# LightBarrier.net
KiCad netlist of a schematic drawn in Altium Designer
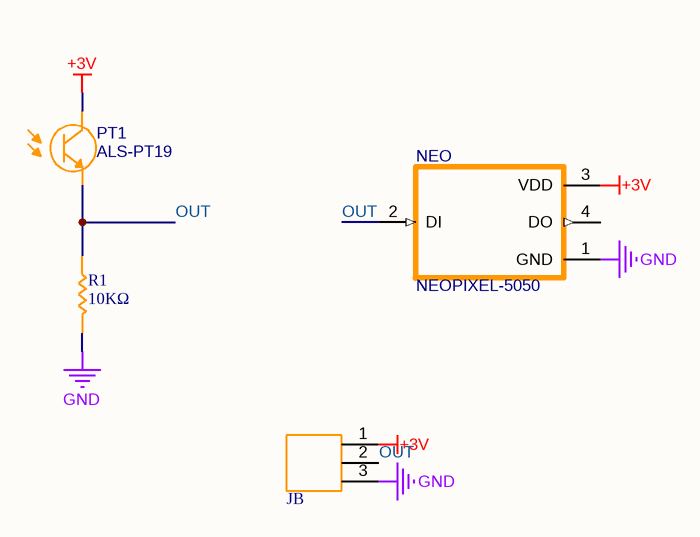
[diagram p0: LightBarrier.SchDoc]

(export (version "E")
  (design (tool "Eeschema 10.0.6"))
  (components
    (comp (ref "JB")
      (value "3PIN")
      (footprint "3PIN")
      (description "2.54 Header")
      (libsource (lib "RC") (part "3PIN"))
    )
    (comp (ref "NEO")
      (value "NEOPIXEL-5050")
      (footprint "NEOPIXEL-5050")
      (libsource (lib "RC") (part "NEOPIXEL-5050"))
    )
    (comp (ref "PT1") (value "ALS-PT19") (footprint "ALS-PT19") (libsource (lib "RC") (part "ALS-PT19")))
    (comp (ref "R1")
      (value "10KΩ")
      (footprint "RES_0603")
      (description "Resistor SMD 0603 generic")
      (libsource (lib "RC") (part "RES_0603"))
    )
  )
  (nets
    (net (code "1") (name "+3V") (class "Default")
      (node (ref "JB") (pin "1") (pinfunction "01_1") (pintype "passive"))
      (node (ref "NEO") (pin "3") (pinfunction "VDD_3") (pintype "power_in"))
      (node (ref "PT1") (pin "C") (pinfunction "C_C") (pintype "passive"))
    )
    (net (code "2") (name "/OUT") (class "Default")
      (node (ref "JB") (pin "2") (pinfunction "02_2") (pintype "passive"))
      (node (ref "NEO") (pin "2") (pinfunction "DI_2") (pintype "input"))
      (node (ref "PT1") (pin "E") (pinfunction "E_E") (pintype "passive"))
      (node (ref "R1") (pin "2") (pintype "passive"))
    )
    (net (code "3") (name "GND") (class "Default")
      (node (ref "JB") (pin "3") (pinfunction "03_3") (pintype "passive"))
      (node (ref "NEO") (pin "1") (pinfunction "GND_1") (pintype "power_in"))
      (node (ref "R1") (pin "1") (pintype "passive"))
    )
    (net (code "4") (name "unconnected-(NEO-DO-Pad4)") (class "Default")
      (node (ref "NEO") (pin "4") (pinfunction "DO_4") (pintype "output"))
    )
  )
)
